# CBB-XBEE-r02.net
KiCad netlist of a schematic drawn in EAGLE
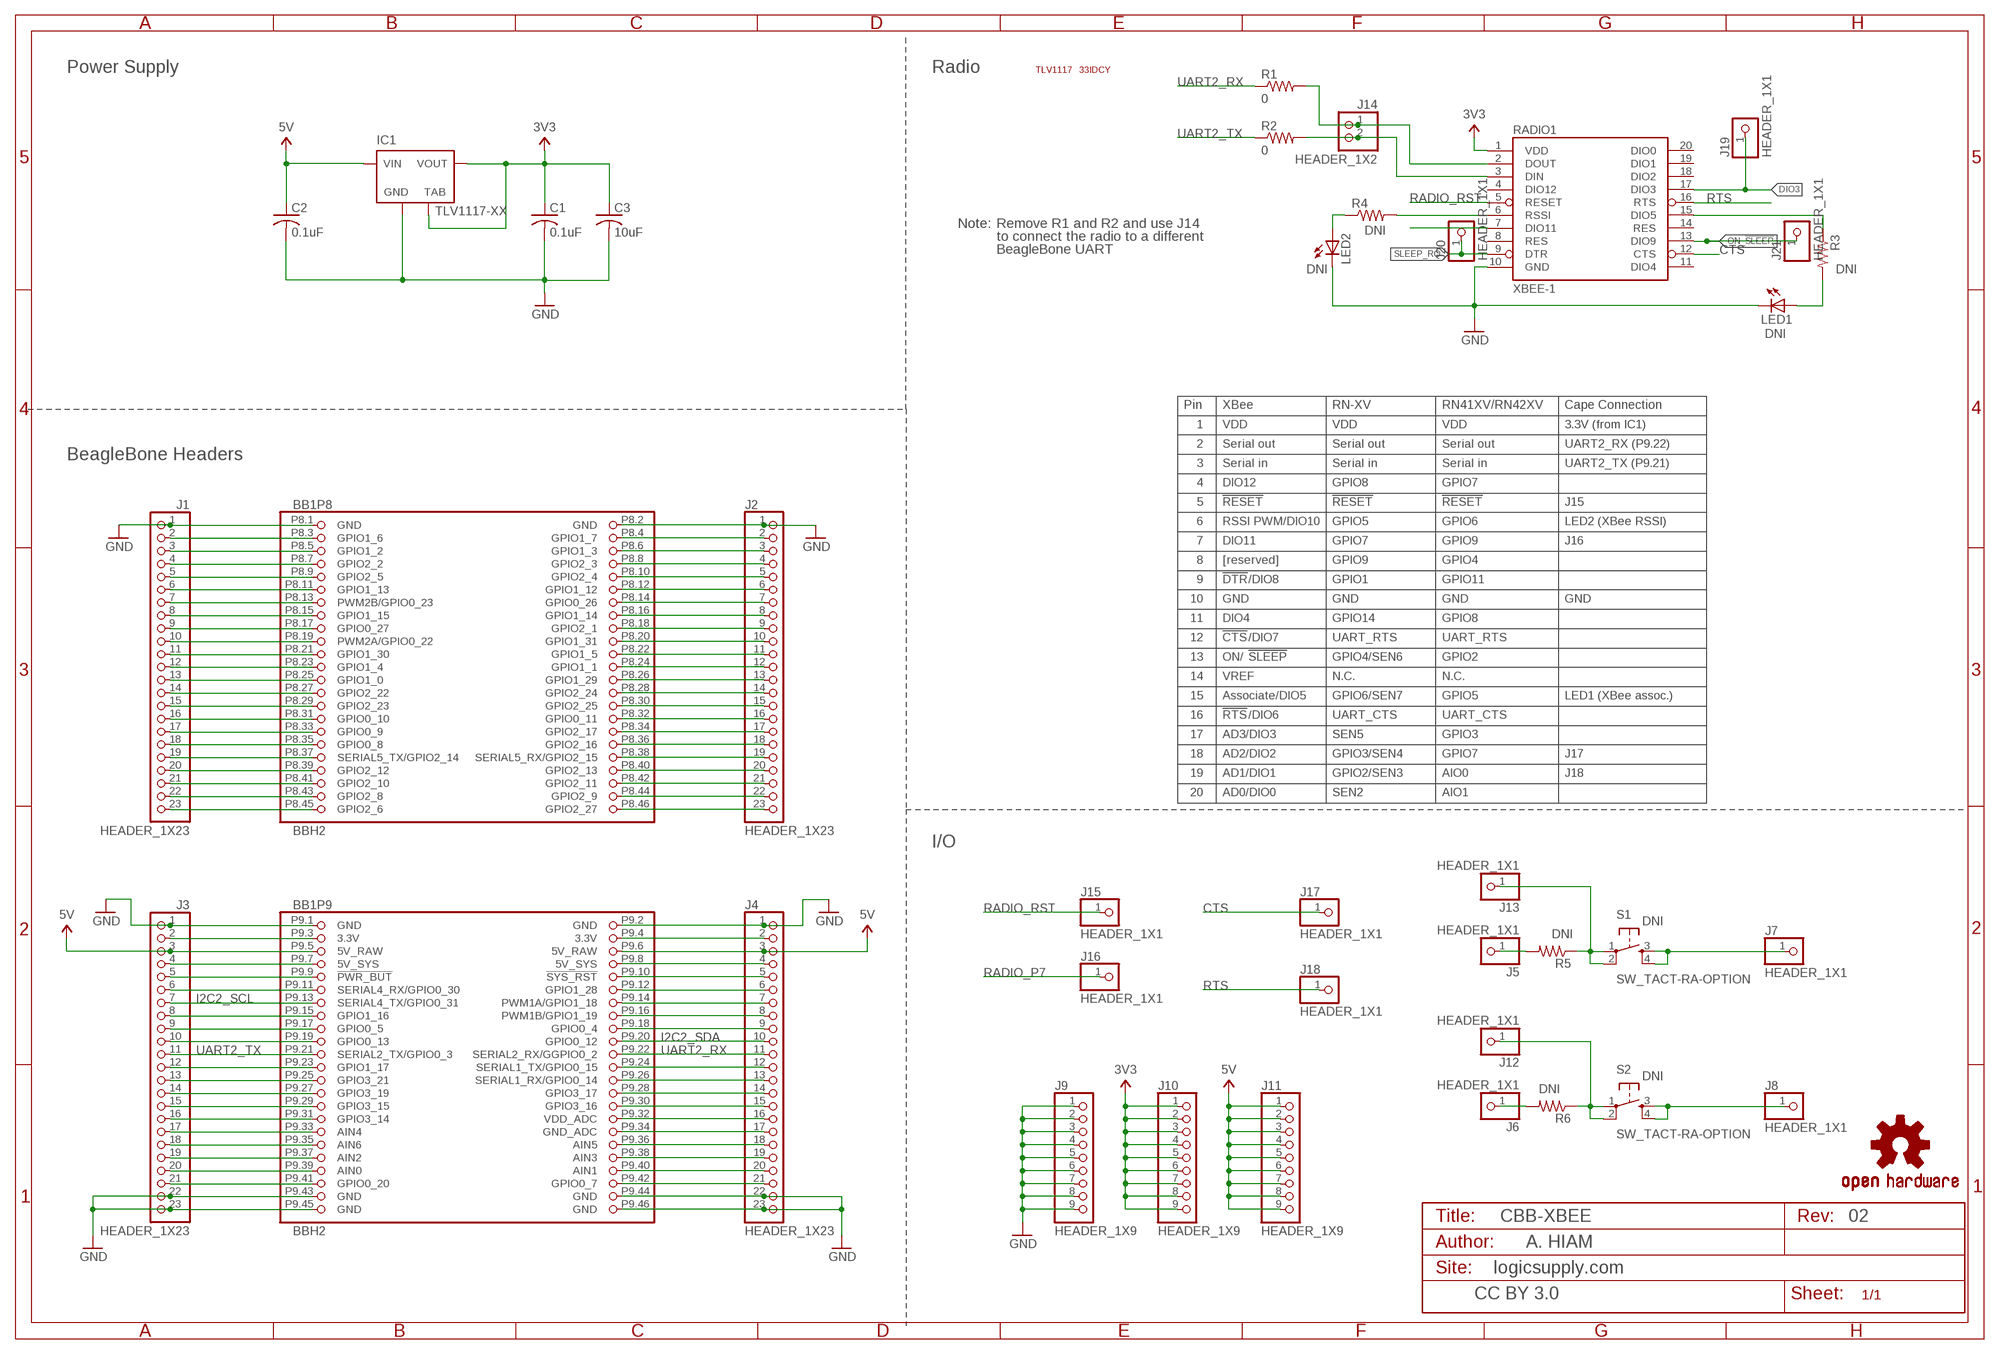
[diagram p0: schematic, sheet 1]

(export (version "E")
  (design (tool "Eeschema 10.0.6"))
  (components
    (comp (ref "BB1")
      (value "BBH2")
      (footprint "eagle-import:BB_CAPE_TOP")
      (libsource (lib "eagle-import") (part "BBH2"))
    )
    (comp (ref "C1")
      (value "0.1uF")
      (footprint "eagle-import:C0805")
      (libsource (lib "eagle-import") (part "C0805"))
    )
    (comp (ref "C2")
      (value "0.1uF")
      (footprint "eagle-import:C0805")
      (libsource (lib "eagle-import") (part "C0805"))
    )
    (comp (ref "C3")
      (value "10uF")
      (footprint "eagle-import:C0805")
      (libsource (lib "eagle-import") (part "C0805"))
    )
    (comp (ref "IC1")
      (value "TLV1117-XX")
      (footprint "eagle-import:SOT223")
      (libsource (lib "eagle-import") (part "TLV1117-XX"))
    )
    (comp (ref "J1")
      (value "HEADER_1X23")
      (footprint "eagle-import:HEADER_1X23")
      (libsource (lib "eagle-import") (part "HEADER_1X23"))
    )
    (comp (ref "J2")
      (value "HEADER_1X23")
      (footprint "eagle-import:HEADER_1X23")
      (libsource (lib "eagle-import") (part "HEADER_1X23"))
    )
    (comp (ref "J3")
      (value "HEADER_1X23")
      (footprint "eagle-import:HEADER_1X23")
      (libsource (lib "eagle-import") (part "HEADER_1X23"))
    )
    (comp (ref "J4")
      (value "HEADER_1X23")
      (footprint "eagle-import:HEADER_1X23")
      (libsource (lib "eagle-import") (part "HEADER_1X23"))
    )
    (comp (ref "J5")
      (value "HEADER_1X1")
      (footprint "eagle-import:HEADER_1X1")
      (libsource (lib "eagle-import") (part "HEADER_1X1"))
    )
    (comp (ref "J6")
      (value "HEADER_1X1")
      (footprint "eagle-import:HEADER_1X1")
      (libsource (lib "eagle-import") (part "HEADER_1X1"))
    )
    (comp (ref "J7")
      (value "HEADER_1X1")
      (footprint "eagle-import:HEADER_1X1")
      (libsource (lib "eagle-import") (part "HEADER_1X1"))
    )
    (comp (ref "J8")
      (value "HEADER_1X1")
      (footprint "eagle-import:HEADER_1X1")
      (libsource (lib "eagle-import") (part "HEADER_1X1"))
    )
    (comp (ref "J9")
      (value "HEADER_1X9")
      (footprint "eagle-import:HEADER_1X9")
      (libsource (lib "eagle-import") (part "HEADER_1X9"))
    )
    (comp (ref "J10")
      (value "HEADER_1X9")
      (footprint "eagle-import:HEADER_1X9")
      (libsource (lib "eagle-import") (part "HEADER_1X9"))
    )
    (comp (ref "J11")
      (value "HEADER_1X9")
      (footprint "eagle-import:HEADER_1X9")
      (libsource (lib "eagle-import") (part "HEADER_1X9"))
    )
    (comp (ref "J12")
      (value "HEADER_1X1")
      (footprint "eagle-import:HEADER_1X1")
      (libsource (lib "eagle-import") (part "HEADER_1X1"))
    )
    (comp (ref "J13")
      (value "HEADER_1X1")
      (footprint "eagle-import:HEADER_1X1")
      (libsource (lib "eagle-import") (part "HEADER_1X1"))
    )
    (comp (ref "J14")
      (value "HEADER_1X2")
      (footprint "eagle-import:HEADER_1X2")
      (libsource (lib "eagle-import") (part "HEADER_1X2"))
    )
    (comp (ref "J15")
      (value "HEADER_1X1")
      (footprint "eagle-import:HEADER_1X1")
      (libsource (lib "eagle-import") (part "HEADER_1X1"))
    )
    (comp (ref "J16")
      (value "HEADER_1X1")
      (footprint "eagle-import:HEADER_1X1")
      (libsource (lib "eagle-import") (part "HEADER_1X1"))
    )
    (comp (ref "J17")
      (value "HEADER_1X1")
      (footprint "eagle-import:HEADER_1X1")
      (libsource (lib "eagle-import") (part "HEADER_1X1"))
    )
    (comp (ref "J18")
      (value "HEADER_1X1")
      (footprint "eagle-import:HEADER_1X1")
      (libsource (lib "eagle-import") (part "HEADER_1X1"))
    )
    (comp (ref "J19")
      (value "HEADER_1X1")
      (footprint "eagle-import:HEADER_1X1")
      (libsource (lib "eagle-import") (part "HEADER_1X1"))
    )
    (comp (ref "J20")
      (value "HEADER_1X1")
      (footprint "eagle-import:HEADER_1X1")
      (libsource (lib "eagle-import") (part "HEADER_1X1"))
    )
    (comp (ref "J21")
      (value "HEADER_1X1")
      (footprint "eagle-import:HEADER_1X1")
      (libsource (lib "eagle-import") (part "HEADER_1X1"))
    )
    (comp (ref "LED1")
      (value "LEDCHIPLED_0805")
      (footprint "eagle-import:CHIPLED_0805")
      (libsource (lib "eagle-import") (part "LEDCHIPLED_0805"))
    )
    (comp (ref "LED2")
      (value "LEDCHIPLED_0805")
      (footprint "eagle-import:CHIPLED_0805")
      (libsource (lib "eagle-import") (part "LEDCHIPLED_0805"))
    )
    (comp (ref "R1")
      (value "0")
      (footprint "eagle-import:R0805")
      (libsource (lib "eagle-import") (part "R0805"))
    )
    (comp (ref "R2")
      (value "0")
      (footprint "eagle-import:R0805")
      (libsource (lib "eagle-import") (part "R0805"))
    )
    (comp (ref "R3")
      (value "R0805")
      (footprint "eagle-import:R0805")
      (libsource (lib "eagle-import") (part "R0805"))
    )
    (comp (ref "R4")
      (value "R0805")
      (footprint "eagle-import:R0805")
      (libsource (lib "eagle-import") (part "R0805"))
    )
    (comp (ref "R5")
      (value "R0207/10")
      (footprint "eagle-import:0207_10")
      (libsource (lib "eagle-import") (part "R0207/10"))
    )
    (comp (ref "R6")
      (value "R0207/10")
      (footprint "eagle-import:0207_10")
      (libsource (lib "eagle-import") (part "R0207/10"))
    )
    (comp (ref "RADIO1")
      (value "XBEE-1")
      (footprint "eagle-import:XBEE")
      (libsource (lib "eagle-import") (part "XBEE-1"))
    )
    (comp (ref "S1")
      (value "SW_TACT-RA-OPTION")
      (footprint "eagle-import:TACT-PTH-RA-OPTION")
      (libsource (lib "eagle-import") (part "SW_TACT-RA-OPTION"))
    )
    (comp (ref "S2")
      (value "SW_TACT-RA-OPTION")
      (footprint "eagle-import:TACT-PTH-RA-OPTION")
      (libsource (lib "eagle-import") (part "SW_TACT-RA-OPTION"))
    )
    (comp (ref "U$7")
      (value "OSHW-LOGOM")
      (footprint "eagle-import:OSHW-LOGO-M")
      (libsource (lib "eagle-import") (part "OSHW-LOGOM"))
    )
  )
  (nets
    (net (code "1") (name "/CTS") (class "Default")
      (node (ref "J17") (pin "1") (pinfunction "1_1") (pintype "passive"))
      (node (ref "RADIO1") (pin "12") (pinfunction "CTS_12") (pintype "output"))
    )
    (net (code "2") (name "/I2C2_SCL") (class "Default")
      (node (ref "BB1") (pin "P9.19") (pinfunction "GPIO0_13_P9.19") (pintype "bidirectional"))
      (node (ref "J3") (pin "10") (pinfunction "10_10") (pintype "passive"))
    )
    (net (code "3") (name "/I2C2_SDA") (class "Default")
      (node (ref "BB1") (pin "P9.20") (pinfunction "GPIO0_12_P9.20") (pintype "bidirectional"))
      (node (ref "J4") (pin "10") (pinfunction "10_10") (pintype "passive"))
    )
    (net (code "4") (name "/ON_~{SLEEP}") (class "Default")
      (node (ref "J21") (pin "1") (pinfunction "1_1") (pintype "passive"))
      (node (ref "RADIO1") (pin "13") (pinfunction "DIO9_13") (pintype "bidirectional"))
    )
    (net (code "5") (name "/RADIO_P7") (class "Default")
      (node (ref "J16") (pin "1") (pinfunction "1_1") (pintype "passive"))
      (node (ref "RADIO1") (pin "7") (pinfunction "DIO11_7") (pintype "bidirectional"))
    )
    (net (code "6") (name "/RADIO_RST") (class "Default")
      (node (ref "J15") (pin "1") (pinfunction "1_1") (pintype "passive"))
      (node (ref "RADIO1") (pin "5") (pinfunction "RESET_5") (pintype "input"))
    )
    (net (code "7") (name "/RTS") (class "Default")
      (node (ref "J18") (pin "1") (pinfunction "1_1") (pintype "passive"))
      (node (ref "RADIO1") (pin "16") (pinfunction "RTS_16") (pintype "input"))
    )
    (net (code "8") (name "/UART2_RX") (class "Default")
      (node (ref "BB1") (pin "P9.22") (pinfunction "SERIAL2_RX/GGPIO0_2_P9.22") (pintype "bidirectional"))
      (node (ref "J4") (pin "11") (pinfunction "11_11") (pintype "passive"))
      (node (ref "R1") (pin "1") (pinfunction "1_1") (pintype "passive"))
    )
    (net (code "9") (name "/UART2_TX") (class "Default")
      (node (ref "BB1") (pin "P9.21") (pinfunction "SERIAL2_TX/GPIO0_3_P9.21") (pintype "bidirectional"))
      (node (ref "J3") (pin "11") (pinfunction "11_11") (pintype "passive"))
      (node (ref "R2") (pin "1") (pinfunction "1_1") (pintype "passive"))
    )
    (net (code "10") (name "3V3") (class "Default")
      (node (ref "C1") (pin "1") (pinfunction "1_1") (pintype "passive"))
      (node (ref "C3") (pin "1") (pinfunction "1_1") (pintype "passive"))
      (node (ref "IC1") (pin "2") (pinfunction "VOUT_2") (pintype "bidirectional"))
      (node (ref "IC1") (pin "4") (pinfunction "TAB_4") (pintype "bidirectional"))
      (node (ref "J10") (pin "1") (pinfunction "1_1") (pintype "passive"))
      (node (ref "J10") (pin "2") (pinfunction "2_2") (pintype "passive"))
      (node (ref "J10") (pin "3") (pinfunction "3_3") (pintype "passive"))
      (node (ref "J10") (pin "4") (pinfunction "4_4") (pintype "passive"))
      (node (ref "J10") (pin "5") (pinfunction "5_5") (pintype "passive"))
      (node (ref "J10") (pin "6") (pinfunction "6_6") (pintype "passive"))
      (node (ref "J10") (pin "7") (pinfunction "7_7") (pintype "passive"))
      (node (ref "J10") (pin "8") (pinfunction "8_8") (pintype "passive"))
      (node (ref "J10") (pin "9") (pinfunction "9_9") (pintype "passive"))
      (node (ref "RADIO1") (pin "1") (pinfunction "VDD_1") (pintype "power_in"))
    )
    (net (code "11") (name "5V") (class "Default")
      (node (ref "BB1") (pin "P9.5") (pinfunction "5V_RAW_P9.5") (pintype "power_in"))
      (node (ref "BB1") (pin "P9.6") (pinfunction "5V_RAW_P9.6") (pintype "power_in"))
      (node (ref "C2") (pin "1") (pinfunction "1_1") (pintype "passive"))
      (node (ref "IC1") (pin "3") (pinfunction "VIN_3") (pintype "bidirectional"))
      (node (ref "J11") (pin "1") (pinfunction "1_1") (pintype "passive"))
      (node (ref "J11") (pin "2") (pinfunction "2_2") (pintype "passive"))
      (node (ref "J11") (pin "3") (pinfunction "3_3") (pintype "passive"))
      (node (ref "J11") (pin "4") (pinfunction "4_4") (pintype "passive"))
      (node (ref "J11") (pin "5") (pinfunction "5_5") (pintype "passive"))
      (node (ref "J11") (pin "6") (pinfunction "6_6") (pintype "passive"))
      (node (ref "J11") (pin "7") (pinfunction "7_7") (pintype "passive"))
      (node (ref "J11") (pin "8") (pinfunction "8_8") (pintype "passive"))
      (node (ref "J11") (pin "9") (pinfunction "9_9") (pintype "passive"))
      (node (ref "J3") (pin "3") (pinfunction "3_3") (pintype "passive"))
      (node (ref "J4") (pin "3") (pinfunction "3_3") (pintype "passive"))
    )
    (net (code "12") (name "DIO3") (class "Default")
      (node (ref "J19") (pin "1") (pinfunction "1_1") (pintype "passive"))
      (node (ref "RADIO1") (pin "17") (pinfunction "DIO3_17") (pintype "bidirectional"))
    )
    (net (code "13") (name "GND") (class "Default")
      (node (ref "BB1") (pin "P8.1") (pinfunction "GND_P8.1") (pintype "power_in"))
      (node (ref "BB1") (pin "P8.2") (pinfunction "GND_P8.2") (pintype "power_in"))
      (node (ref "BB1") (pin "P9.1") (pinfunction "GND_P9.1") (pintype "power_in"))
      (node (ref "BB1") (pin "P9.2") (pinfunction "GND_P9.2") (pintype "power_in"))
      (node (ref "BB1") (pin "P9.43") (pinfunction "GND_P9.43") (pintype "bidirectional"))
      (node (ref "BB1") (pin "P9.44") (pinfunction "GND_P9.44") (pintype "bidirectional"))
      (node (ref "BB1") (pin "P9.45") (pinfunction "GND_P9.45") (pintype "bidirectional"))
      (node (ref "BB1") (pin "P9.46") (pinfunction "GND_P9.46") (pintype "bidirectional"))
      (node (ref "C1") (pin "2") (pinfunction "2_2") (pintype "passive"))
      (node (ref "C2") (pin "2") (pinfunction "2_2") (pintype "passive"))
      (node (ref "C3") (pin "2") (pinfunction "2_2") (pintype "passive"))
      (node (ref "IC1") (pin "1") (pinfunction "GND_1") (pintype "bidirectional"))
      (node (ref "J1") (pin "1") (pinfunction "1_1") (pintype "passive"))
      (node (ref "J2") (pin "1") (pinfunction "1_1") (pintype "passive"))
      (node (ref "J3") (pin "1") (pinfunction "1_1") (pintype "passive"))
      (node (ref "J3") (pin "22") (pinfunction "22_22") (pintype "passive"))
      (node (ref "J3") (pin "23") (pinfunction "23_23") (pintype "passive"))
      (node (ref "J4") (pin "1") (pinfunction "1_1") (pintype "passive"))
      (node (ref "J4") (pin "22") (pinfunction "22_22") (pintype "passive"))
      (node (ref "J4") (pin "23") (pinfunction "23_23") (pintype "passive"))
      (node (ref "J9") (pin "1") (pinfunction "1_1") (pintype "passive"))
      (node (ref "J9") (pin "2") (pinfunction "2_2") (pintype "passive"))
      (node (ref "J9") (pin "3") (pinfunction "3_3") (pintype "passive"))
      (node (ref "J9") (pin "4") (pinfunction "4_4") (pintype "passive"))
      (node (ref "J9") (pin "5") (pinfunction "5_5") (pintype "passive"))
      (node (ref "J9") (pin "6") (pinfunction "6_6") (pintype "passive"))
      (node (ref "J9") (pin "7") (pinfunction "7_7") (pintype "passive"))
      (node (ref "J9") (pin "8") (pinfunction "8_8") (pintype "passive"))
      (node (ref "J9") (pin "9") (pinfunction "9_9") (pintype "passive"))
      (node (ref "LED1") (pin "C") (pinfunction "C_C") (pintype "passive"))
      (node (ref "LED2") (pin "C") (pinfunction "C_C") (pintype "passive"))
      (node (ref "RADIO1") (pin "10") (pinfunction "GND_10") (pintype "power_in"))
    )
    (net (code "14") (name "Net-(BB1A-GPIO0_8)") (class "Default")
      (node (ref "BB1") (pin "P8.35") (pinfunction "GPIO0_8_P8.35") (pintype "bidirectional"))
      (node (ref "J1") (pin "18") (pinfunction "18_18") (pintype "passive"))
    )
    (net (code "15") (name "Net-(BB1A-GPIO0_9)") (class "Default")
      (node (ref "BB1") (pin "P8.33") (pinfunction "GPIO0_9_P8.33") (pintype "bidirectional"))
      (node (ref "J1") (pin "17") (pinfunction "17_17") (pintype "passive"))
    )
    (net (code "16") (name "Net-(BB1A-GPIO0_10)") (class "Default")
      (node (ref "BB1") (pin "P8.31") (pinfunction "GPIO0_10_P8.31") (pintype "bidirectional"))
      (node (ref "J1") (pin "16") (pinfunction "16_16") (pintype "passive"))
    )
    (net (code "17") (name "Net-(BB1A-GPIO0_11)") (class "Default")
      (node (ref "BB1") (pin "P8.32") (pinfunction "GPIO0_11_P8.32") (pintype "bidirectional"))
      (node (ref "J2") (pin "16") (pinfunction "16_16") (pintype "passive"))
    )
    (net (code "18") (name "Net-(BB1A-GPIO0_26)") (class "Default")
      (node (ref "BB1") (pin "P8.14") (pinfunction "GPIO0_26_P8.14") (pintype "bidirectional"))
      (node (ref "J2") (pin "7") (pinfunction "7_7") (pintype "passive"))
    )
    (net (code "19") (name "Net-(BB1A-GPIO0_27)") (class "Default")
      (node (ref "BB1") (pin "P8.17") (pinfunction "GPIO0_27_P8.17") (pintype "bidirectional"))
      (node (ref "J1") (pin "9") (pinfunction "9_9") (pintype "passive"))
    )
    (net (code "20") (name "Net-(BB1A-GPIO1_0)") (class "Default")
      (node (ref "BB1") (pin "P8.25") (pinfunction "GPIO1_0_P8.25") (pintype "bidirectional"))
      (node (ref "J1") (pin "13") (pinfunction "13_13") (pintype "passive"))
    )
    (net (code "21") (name "Net-(BB1A-GPIO1_1)") (class "Default")
      (node (ref "BB1") (pin "P8.24") (pinfunction "GPIO1_1_P8.24") (pintype "bidirectional"))
      (node (ref "J2") (pin "12") (pinfunction "12_12") (pintype "passive"))
    )
    (net (code "22") (name "Net-(BB1A-GPIO1_2)") (class "Default")
      (node (ref "BB1") (pin "P8.5") (pinfunction "GPIO1_2_P8.5") (pintype "bidirectional"))
      (node (ref "J1") (pin "3") (pinfunction "3_3") (pintype "passive"))
    )
    (net (code "23") (name "Net-(BB1A-GPIO1_3)") (class "Default")
      (node (ref "BB1") (pin "P8.6") (pinfunction "GPIO1_3_P8.6") (pintype "bidirectional"))
      (node (ref "J2") (pin "3") (pinfunction "3_3") (pintype "passive"))
    )
    (net (code "24") (name "Net-(BB1A-GPIO1_4)") (class "Default")
      (node (ref "BB1") (pin "P8.23") (pinfunction "GPIO1_4_P8.23") (pintype "bidirectional"))
      (node (ref "J1") (pin "12") (pinfunction "12_12") (pintype "passive"))
    )
    (net (code "25") (name "Net-(BB1A-GPIO1_5)") (class "Default")
      (node (ref "BB1") (pin "P8.22") (pinfunction "GPIO1_5_P8.22") (pintype "bidirectional"))
      (node (ref "J2") (pin "11") (pinfunction "11_11") (pintype "passive"))
    )
    (net (code "26") (name "Net-(BB1A-GPIO1_6)") (class "Default")
      (node (ref "BB1") (pin "P8.3") (pinfunction "GPIO1_6_P8.3") (pintype "bidirectional"))
      (node (ref "J1") (pin "2") (pinfunction "2_2") (pintype "passive"))
    )
    (net (code "27") (name "Net-(BB1A-GPIO1_7)") (class "Default")
      (node (ref "BB1") (pin "P8.4") (pinfunction "GPIO1_7_P8.4") (pintype "bidirectional"))
      (node (ref "J2") (pin "2") (pinfunction "2_2") (pintype "passive"))
    )
    (net (code "28") (name "Net-(BB1A-GPIO1_12)") (class "Default")
      (node (ref "BB1") (pin "P8.12") (pinfunction "GPIO1_12_P8.12") (pintype "bidirectional"))
      (node (ref "J2") (pin "6") (pinfunction "6_6") (pintype "passive"))
    )
    (net (code "29") (name "Net-(BB1A-GPIO1_13)") (class "Default")
      (node (ref "BB1") (pin "P8.11") (pinfunction "GPIO1_13_P8.11") (pintype "bidirectional"))
      (node (ref "J1") (pin "6") (pinfunction "6_6") (pintype "passive"))
    )
    (net (code "30") (name "Net-(BB1A-GPIO1_14)") (class "Default")
      (node (ref "BB1") (pin "P8.16") (pinfunction "GPIO1_14_P8.16") (pintype "bidirectional"))
      (node (ref "J2") (pin "8") (pinfunction "8_8") (pintype "passive"))
    )
    (net (code "31") (name "Net-(BB1A-GPIO1_15)") (class "Default")
      (node (ref "BB1") (pin "P8.15") (pinfunction "GPIO1_15_P8.15") (pintype "bidirectional"))
      (node (ref "J1") (pin "8") (pinfunction "8_8") (pintype "passive"))
    )
    (net (code "32") (name "Net-(BB1A-GPIO1_29)") (class "Default")
      (node (ref "BB1") (pin "P8.26") (pinfunction "GPIO1_29_P8.26") (pintype "bidirectional"))
      (node (ref "J2") (pin "13") (pinfunction "13_13") (pintype "passive"))
    )
    (net (code "33") (name "Net-(BB1A-GPIO1_30)") (class "Default")
      (node (ref "BB1") (pin "P8.21") (pinfunction "GPIO1_30_P8.21") (pintype "bidirectional"))
      (node (ref "J1") (pin "11") (pinfunction "11_11") (pintype "passive"))
    )
    (net (code "34") (name "Net-(BB1A-GPIO1_31)") (class "Default")
      (node (ref "BB1") (pin "P8.20") (pinfunction "GPIO1_31_P8.20") (pintype "bidirectional"))
      (node (ref "J2") (pin "10") (pinfunction "10_10") (pintype "passive"))
    )
    (net (code "35") (name "Net-(BB1A-GPIO2_1)") (class "Default")
      (node (ref "BB1") (pin "P8.18") (pinfunction "GPIO2_1_P8.18") (pintype "bidirectional"))
      (node (ref "J2") (pin "9") (pinfunction "9_9") (pintype "passive"))
    )
    (net (code "36") (name "Net-(BB1A-GPIO2_2)") (class "Default")
      (node (ref "BB1") (pin "P8.7") (pinfunction "GPIO2_2_P8.7") (pintype "bidirectional"))
      (node (ref "J1") (pin "4") (pinfunction "4_4") (pintype "passive"))
    )
    (net (code "37") (name "Net-(BB1A-GPIO2_3)") (class "Default")
      (node (ref "BB1") (pin "P8.8") (pinfunction "GPIO2_3_P8.8") (pintype "bidirectional"))
      (node (ref "J2") (pin "4") (pinfunction "4_4") (pintype "passive"))
    )
    (net (code "38") (name "Net-(BB1A-GPIO2_4)") (class "Default")
      (node (ref "BB1") (pin "P8.10") (pinfunction "GPIO2_4_P8.10") (pintype "bidirectional"))
      (node (ref "J2") (pin "5") (pinfunction "5_5") (pintype "passive"))
    )
    (net (code "39") (name "Net-(BB1A-GPIO2_5)") (class "Default")
      (node (ref "BB1") (pin "P8.9") (pinfunction "GPIO2_5_P8.9") (pintype "bidirectional"))
      (node (ref "J1") (pin "5") (pinfunction "5_5") (pintype "passive"))
    )
    (net (code "40") (name "Net-(BB1A-GPIO2_6)") (class "Default")
      (node (ref "BB1") (pin "P8.45") (pinfunction "GPIO2_6_P8.45") (pintype "bidirectional"))
      (node (ref "J1") (pin "23") (pinfunction "23_23") (pintype "passive"))
    )
    (net (code "41") (name "Net-(BB1A-GPIO2_8)") (class "Default")
      (node (ref "BB1") (pin "P8.43") (pinfunction "GPIO2_8_P8.43") (pintype "bidirectional"))
      (node (ref "J1") (pin "22") (pinfunction "22_22") (pintype "passive"))
    )
    (net (code "42") (name "Net-(BB1A-GPIO2_9)") (class "Default")
      (node (ref "BB1") (pin "P8.44") (pinfunction "GPIO2_9_P8.44") (pintype "bidirectional"))
      (node (ref "J2") (pin "22") (pinfunction "22_22") (pintype "passive"))
    )
    (net (code "43") (name "Net-(BB1A-GPIO2_10)") (class "Default")
      (node (ref "BB1") (pin "P8.41") (pinfunction "GPIO2_10_P8.41") (pintype "bidirectional"))
      (node (ref "J1") (pin "21") (pinfunction "21_21") (pintype "passive"))
    )
    (net (code "44") (name "Net-(BB1A-GPIO2_11)") (class "Default")
      (node (ref "BB1") (pin "P8.42") (pinfunction "GPIO2_11_P8.42") (pintype "bidirectional"))
      (node (ref "J2") (pin "21") (pinfunction "21_21") (pintype "passive"))
    )
    (net (code "45") (name "Net-(BB1A-GPIO2_12)") (class "Default")
      (node (ref "BB1") (pin "P8.39") (pinfunction "GPIO2_12_P8.39") (pintype "bidirectional"))
      (node (ref "J1") (pin "20") (pinfunction "20_20") (pintype "passive"))
    )
    (net (code "46") (name "Net-(BB1A-GPIO2_13)") (class "Default")
      (node (ref "BB1") (pin "P8.40") (pinfunction "GPIO2_13_P8.40") (pintype "bidirectional"))
      (node (ref "J2") (pin "20") (pinfunction "20_20") (pintype "passive"))
    )
    (net (code "47") (name "Net-(BB1A-GPIO2_16)") (class "Default")
      (node (ref "BB1") (pin "P8.36") (pinfunction "GPIO2_16_P8.36") (pintype "bidirectional"))
      (node (ref "J2") (pin "18") (pinfunction "18_18") (pintype "passive"))
    )
    (net (code "48") (name "Net-(BB1A-GPIO2_17)") (class "Default")
      (node (ref "BB1") (pin "P8.34") (pinfunction "GPIO2_17_P8.34") (pintype "bidirectional"))
      (node (ref "J2") (pin "17") (pinfunction "17_17") (pintype "passive"))
    )
    (net (code "49") (name "Net-(BB1A-GPIO2_22)") (class "Default")
      (node (ref "BB1") (pin "P8.27") (pinfunction "GPIO2_22_P8.27") (pintype "bidirectional"))
      (node (ref "J1") (pin "14") (pinfunction "14_14") (pintype "passive"))
    )
    (net (code "50") (name "Net-(BB1A-GPIO2_23)") (class "Default")
      (node (ref "BB1") (pin "P8.29") (pinfunction "GPIO2_23_P8.29") (pintype "bidirectional"))
      (node (ref "J1") (pin "15") (pinfunction "15_15") (pintype "passive"))
    )
    (net (code "51") (name "Net-(BB1A-GPIO2_24)") (class "Default")
      (node (ref "BB1") (pin "P8.28") (pinfunction "GPIO2_24_P8.28") (pintype "bidirectional"))
      (node (ref "J2") (pin "14") (pinfunction "14_14") (pintype "passive"))
    )
    (net (code "52") (name "Net-(BB1A-GPIO2_25)") (class "Default")
      (node (ref "BB1") (pin "P8.30") (pinfunction "GPIO2_25_P8.30") (pintype "bidirectional"))
      (node (ref "J2") (pin "15") (pinfunction "15_15") (pintype "passive"))
    )
    (net (code "53") (name "Net-(BB1A-GPIO2_27)") (class "Default")
      (node (ref "BB1") (pin "P8.46") (pinfunction "GPIO2_27_P8.46") (pintype "bidirectional"))
      (node (ref "J2") (pin "23") (pinfunction "23_23") (pintype "passive"))
    )
    (net (code "54") (name "Net-(BB1A-PWM2A{slash}GPIO0_22)") (class "Default")
      (node (ref "BB1") (pin "P8.19") (pinfunction "PWM2A/GPIO0_22_P8.19") (pintype "bidirectional"))
      (node (ref "J1") (pin "10") (pinfunction "10_10") (pintype "passive"))
    )
    (net (code "55") (name "Net-(BB1A-PWM2B{slash}GPIO0_23)") (class "Default")
      (node (ref "BB1") (pin "P8.13") (pinfunction "PWM2B/GPIO0_23_P8.13") (pintype "bidirectional"))
      (node (ref "J1") (pin "7") (pinfunction "7_7") (pintype "passive"))
    )
    (net (code "56") (name "Net-(BB1A-SERIAL5_RX{slash}GPIO2_15)") (class "Default")
      (node (ref "BB1") (pin "P8.38") (pinfunction "SERIAL5_RX/GPIO2_15_P8.38") (pintype "bidirectional"))
      (node (ref "J2") (pin "19") (pinfunction "19_19") (pintype "passive"))
    )
    (net (code "57") (name "Net-(BB1A-SERIAL5_TX{slash}GPIO2_14)") (class "Default")
      (node (ref "BB1") (pin "P8.37") (pinfunction "SERIAL5_TX/GPIO2_14_P8.37") (pintype "bidirectional"))
      (node (ref "J1") (pin "19") (pinfunction "19_19") (pintype "passive"))
    )
    (net (code "58") (name "Net-(BB1B-3.3V-PadP9.3)") (class "Default")
      (node (ref "BB1") (pin "P9.3") (pinfunction "3.3V_P9.3") (pintype "power_in"))
      (node (ref "J3") (pin "2") (pinfunction "2_2") (pintype "passive"))
    )
    (net (code "59") (name "Net-(BB1B-3.3V-PadP9.4)") (class "Default")
      (node (ref "BB1") (pin "P9.4") (pinfunction "3.3V_P9.4") (pintype "power_in"))
      (node (ref "J4") (pin "2") (pinfunction "2_2") (pintype "passive"))
    )
    (net (code "60") (name "Net-(BB1B-5V_SYS-PadP9.7)") (class "Default")
      (node (ref "BB1") (pin "P9.7") (pinfunction "5V_SYS_P9.7") (pintype "power_in"))
      (node (ref "J3") (pin "4") (pinfunction "4_4") (pintype "passive"))
    )
    (net (code "61") (name "Net-(BB1B-5V_SYS-PadP9.8)") (class "Default")
      (node (ref "BB1") (pin "P9.8") (pinfunction "5V_SYS_P9.8") (pintype "power_in"))
      (node (ref "J4") (pin "4") (pinfunction "4_4") (pintype "passive"))
    )
    (net (code "62") (name "Net-(BB1B-AIN0)") (class "Default")
      (node (ref "BB1") (pin "P9.39") (pinfunction "AIN0_P9.39") (pintype "input"))
      (node (ref "J3") (pin "20") (pinfunction "20_20") (pintype "passive"))
    )
    (net (code "63") (name "Net-(BB1B-AIN1)") (class "Default")
      (node (ref "BB1") (pin "P9.40") (pinfunction "AIN1_P9.40") (pintype "input"))
      (node (ref "J4") (pin "20") (pinfunction "20_20") (pintype "passive"))
    )
    (net (code "64") (name "Net-(BB1B-AIN2)") (class "Default")
      (node (ref "BB1") (pin "P9.37") (pinfunction "AIN2_P9.37") (pintype "input"))
      (node (ref "J3") (pin "19") (pinfunction "19_19") (pintype "passive"))
    )
    (net (code "65") (name "Net-(BB1B-AIN3)") (class "Default")
      (node (ref "BB1") (pin "P9.38") (pinfunction "AIN3_P9.38") (pintype "input"))
      (node (ref "J4") (pin "19") (pinfunction "19_19") (pintype "passive"))
    )
    (net (code "66") (name "Net-(BB1B-AIN4)") (class "Default")
      (node (ref "BB1") (pin "P9.33") (pinfunction "AIN4_P9.33") (pintype "input"))
      (node (ref "J3") (pin "17") (pinfunction "17_17") (pintype "passive"))
    )
    (net (code "67") (name "Net-(BB1B-AIN5)") (class "Default")
      (node (ref "BB1") (pin "P9.36") (pinfunction "AIN5_P9.36") (pintype "input"))
      (node (ref "J4") (pin "18") (pinfunction "18_18") (pintype "passive"))
    )
    (net (code "68") (name "Net-(BB1B-AIN6)") (class "Default")
      (node (ref "BB1") (pin "P9.35") (pinfunction "AIN6_P9.35") (pintype "input"))
      (node (ref "J3") (pin "18") (pinfunction "18_18") (pintype "passive"))
    )
    (net (code "69") (name "Net-(BB1B-GND_ADC)") (class "Default")
      (node (ref "BB1") (pin "P9.34") (pinfunction "GND_ADC_P9.34") (pintype "bidirectional"))
      (node (ref "J4") (pin "17") (pinfunction "17_17") (pintype "passive"))
    )
    (net (code "70") (name "Net-(BB1B-GPIO0_4)") (class "Default")
      (node (ref "BB1") (pin "P9.18") (pinfunction "GPIO0_4_P9.18") (pintype "bidirectional"))
      (node (ref "J4") (pin "9") (pinfunction "9_9") (pintype "passive"))
    )
    (net (code "71") (name "Net-(BB1B-GPIO0_5)") (class "Default")
      (node (ref "BB1") (pin "P9.17") (pinfunction "GPIO0_5_P9.17") (pintype "bidirectional"))
      (node (ref "J3") (pin "9") (pinfunction "9_9") (pintype "passive"))
    )
    (net (code "72") (name "Net-(BB1B-GPIO0_7)") (class "Default")
      (node (ref "BB1") (pin "P9.42") (pinfunction "GPIO0_7_P9.42") (pintype "bidirectional"))
      (node (ref "J4") (pin "21") (pinfunction "21_21") (pintype "passive"))
    )
    (net (code "73") (name "Net-(BB1B-GPIO0_20)") (class "Default")
      (node (ref "BB1") (pin "P9.41") (pinfunction "GPIO0_20_P9.41") (pintype "bidirectional"))
      (node (ref "J3") (pin "21") (pinfunction "21_21") (pintype "passive"))
    )
    (net (code "74") (name "Net-(BB1B-GPIO1_16)") (class "Default")
      (node (ref "BB1") (pin "P9.15") (pinfunction "GPIO1_16_P9.15") (pintype "bidirectional"))
      (node (ref "J3") (pin "8") (pinfunction "8_8") (pintype "passive"))
    )
    (net (code "75") (name "Net-(BB1B-GPIO1_17)") (class "Default")
      (node (ref "BB1") (pin "P9.23") (pinfunction "GPIO1_17_P9.23") (pintype "bidirectional"))
      (node (ref "J3") (pin "12") (pinfunction "12_12") (pintype "passive"))
    )
    (net (code "76") (name "Net-(BB1B-GPIO1_28)") (class "Default")
      (node (ref "BB1") (pin "P9.12") (pinfunction "GPIO1_28_P9.12") (pintype "bidirectional"))
      (node (ref "J4") (pin "6") (pinfunction "6_6") (pintype "passive"))
    )
    (net (code "77") (name "Net-(BB1B-GPIO3_14)") (class "Default")
      (node (ref "BB1") (pin "P9.31") (pinfunction "GPIO3_14_P9.31") (pintype "bidirectional"))
      (node (ref "J3") (pin "16") (pinfunction "16_16") (pintype "passive"))
    )
    (net (code "78") (name "Net-(BB1B-GPIO3_15)") (class "Default")
      (node (ref "BB1") (pin "P9.29") (pinfunction "GPIO3_15_P9.29") (pintype "bidirectional"))
      (node (ref "J3") (pin "15") (pinfunction "15_15") (pintype "passive"))
    )
    (net (code "79") (name "Net-(BB1B-GPIO3_16)") (class "Default")
      (node (ref "BB1") (pin "P9.30") (pinfunction "GPIO3_16_P9.30") (pintype "bidirectional"))
      (node (ref "J4") (pin "15") (pinfunction "15_15") (pintype "passive"))
    )
    (net (code "80") (name "Net-(BB1B-GPIO3_17)") (class "Default")
      (node (ref "BB1") (pin "P9.28") (pinfunction "GPIO3_17_P9.28") (pintype "bidirectional"))
      (node (ref "J4") (pin "14") (pinfunction "14_14") (pintype "passive"))
    )
    (net (code "81") (name "Net-(BB1B-GPIO3_19)") (class "Default")
      (node (ref "BB1") (pin "P9.27") (pinfunction "GPIO3_19_P9.27") (pintype "bidirectional"))
      (node (ref "J3") (pin "14") (pinfunction "14_14") (pintype "passive"))
    )
    (net (code "82") (name "Net-(BB1B-GPIO3_21)") (class "Default")
      (node (ref "BB1") (pin "P9.25") (pinfunction "GPIO3_21_P9.25") (pintype "bidirectional"))
      (node (ref "J3") (pin "13") (pinfunction "13_13") (pintype "passive"))
    )
    (net (code "83") (name "Net-(BB1B-PWM1A{slash}GPIO1_18)") (class "Default")
      (node (ref "BB1") (pin "P9.14") (pinfunction "PWM1A/GPIO1_18_P9.14") (pintype "bidirectional"))
      (node (ref "J4") (pin "7") (pinfunction "7_7") (pintype "passive"))
    )
    (net (code "84") (name "Net-(BB1B-PWM1B{slash}GPIO1_19)") (class "Default")
      (node (ref "BB1") (pin "P9.16") (pinfunction "PWM1B/GPIO1_19_P9.16") (pintype "bidirectional"))
      (node (ref "J4") (pin "8") (pinfunction "8_8") (pintype "passive"))
    )
    (net (code "85") (name "Net-(BB1B-SERIAL1_RX{slash}GPIO0_14)") (class "Default")
      (node (ref "BB1") (pin "P9.26") (pinfunction "SERIAL1_RX/GPIO0_14_P9.26") (pintype "bidirectional"))
      (node (ref "J4") (pin "13") (pinfunction "13_13") (pintype "passive"))
    )
    (net (code "86") (name "Net-(BB1B-SERIAL1_TX{slash}GPIO0_15)") (class "Default")
      (node (ref "BB1") (pin "P9.24") (pinfunction "SERIAL1_TX/GPIO0_15_P9.24") (pintype "bidirectional"))
      (node (ref "J4") (pin "12") (pinfunction "12_12") (pintype "passive"))
    )
    (net (code "87") (name "Net-(BB1B-SERIAL4_RX{slash}GPIO0_30)") (class "Default")
      (node (ref "BB1") (pin "P9.11") (pinfunction "SERIAL4_RX/GPIO0_30_P9.11") (pintype "bidirectional"))
      (node (ref "J3") (pin "6") (pinfunction "6_6") (pintype "passive"))
    )
    (net (code "88") (name "Net-(BB1B-SERIAL4_TX{slash}GPIO0_31)") (class "Default")
      (node (ref "BB1") (pin "P9.13") (pinfunction "SERIAL4_TX/GPIO0_31_P9.13") (pintype "bidirectional"))
      (node (ref "J3") (pin "7") (pinfunction "7_7") (pintype "passive"))
    )
    (net (code "89") (name "Net-(BB1B-VDD_ADC)") (class "Default")
      (node (ref "BB1") (pin "P9.32") (pinfunction "VDD_ADC_P9.32") (pintype "bidirectional"))
      (node (ref "J4") (pin "16") (pinfunction "16_16") (pintype "passive"))
    )
    (net (code "90") (name "Net-(BB1B-~{PWR_BUT})") (class "Default")
      (node (ref "BB1") (pin "P9.9") (pinfunction "~{PWR_BUT}_P9.9") (pintype "input"))
      (node (ref "J3") (pin "5") (pinfunction "5_5") (pintype "passive"))
    )
    (net (code "91") (name "Net-(BB1B-~{SYS_RST})") (class "Default")
      (node (ref "BB1") (pin "P9.10") (pinfunction "~{SYS_RST}_P9.10") (pintype "input"))
      (node (ref "J4") (pin "5") (pinfunction "5_5") (pintype "passive"))
    )
    (net (code "92") (name "Net-(J5-Pad1)") (class "Default")
      (node (ref "J5") (pin "1") (pinfunction "1_1") (pintype "passive"))
      (node (ref "R5") (pin "2") (pinfunction "2_2") (pintype "passive"))
    )
    (net (code "93") (name "Net-(J6-Pad1)") (class "Default")
      (node (ref "J6") (pin "1") (pinfunction "1_1") (pintype "passive"))
      (node (ref "R6") (pin "2") (pinfunction "2_2") (pintype "passive"))
    )
    (net (code "94") (name "Net-(J7-Pad1)") (class "Default")
      (node (ref "J7") (pin "1") (pinfunction "1_1") (pintype "passive"))
      (node (ref "S1") (pin "3") (pinfunction "3_3") (pintype "passive"))
      (node (ref "S1") (pin "4") (pinfunction "4_4") (pintype "passive"))
    )
    (net (code "95") (name "Net-(J8-Pad1)") (class "Default")
      (node (ref "J8") (pin "1") (pinfunction "1_1") (pintype "passive"))
      (node (ref "S2") (pin "3") (pinfunction "3_3") (pintype "passive"))
      (node (ref "S2") (pin "4") (pinfunction "4_4") (pintype "passive"))
    )
    (net (code "96") (name "Net-(J12-Pad1)") (class "Default")
      (node (ref "J12") (pin "1") (pinfunction "1_1") (pintype "passive"))
      (node (ref "R6") (pin "1") (pinfunction "1_1") (pintype "passive"))
      (node (ref "S2") (pin "1") (pinfunction "1_1") (pintype "passive"))
      (node (ref "S2") (pin "2") (pinfunction "2_2") (pintype "passive"))
    )
    (net (code "97") (name "Net-(J13-Pad1)") (class "Default")
      (node (ref "J13") (pin "1") (pinfunction "1_1") (pintype "passive"))
      (node (ref "R5") (pin "1") (pinfunction "1_1") (pintype "passive"))
      (node (ref "S1") (pin "1") (pinfunction "1_1") (pintype "passive"))
      (node (ref "S1") (pin "2") (pinfunction "2_2") (pintype "passive"))
    )
    (net (code "98") (name "Net-(LED1-PadA)") (class "Default")
      (node (ref "LED1") (pin "A") (pinfunction "A_A") (pintype "passive"))
      (node (ref "R3") (pin "2") (pinfunction "2_2") (pintype "passive"))
    )
    (net (code "99") (name "Net-(LED2-PadA)") (class "Default")
      (node (ref "LED2") (pin "A") (pinfunction "A_A") (pintype "passive"))
      (node (ref "R4") (pin "1") (pinfunction "1_1") (pintype "passive"))
    )
    (net (code "100") (name "Net-(RADIO1-DIN)") (class "Default")
      (node (ref "J14") (pin "2") (pinfunction "2_2") (pintype "passive"))
      (node (ref "R2") (pin "2") (pinfunction "2_2") (pintype "passive"))
      (node (ref "RADIO1") (pin "3") (pinfunction "DIN_3") (pintype "input"))
    )
    (net (code "101") (name "Net-(RADIO1-DIO5)") (class "Default")
      (node (ref "R3") (pin "1") (pinfunction "1_1") (pintype "passive"))
      (node (ref "RADIO1") (pin "15") (pinfunction "DIO5_15") (pintype "bidirectional"))
    )
    (net (code "102") (name "Net-(RADIO1-DOUT)") (class "Default")
      (node (ref "J14") (pin "1") (pinfunction "1_1") (pintype "passive"))
      (node (ref "R1") (pin "2") (pinfunction "2_2") (pintype "passive"))
      (node (ref "RADIO1") (pin "2") (pinfunction "DOUT_2") (pintype "output"))
    )
    (net (code "103") (name "Net-(RADIO1-RSSI)") (class "Default")
      (node (ref "R4") (pin "2") (pinfunction "2_2") (pintype "passive"))
      (node (ref "RADIO1") (pin "6") (pinfunction "RSSI_6") (pintype "bidirectional"))
    )
    (net (code "104") (name "SLEEP_RQ") (class "Default")
      (node (ref "J20") (pin "1") (pinfunction "1_1") (pintype "passive"))
      (node (ref "RADIO1") (pin "9") (pinfunction "DTR_9") (pintype "bidirectional"))
    )
    (net (code "105") (name "unconnected-(RADIO1-DIO0-Pad20)") (class "Default")
      (node (ref "RADIO1") (pin "20") (pinfunction "DIO0_20") (pintype "bidirectional"))
    )
    (net (code "106") (name "unconnected-(RADIO1-DIO1-Pad19)") (class "Default")
      (node (ref "RADIO1") (pin "19") (pinfunction "DIO1_19") (pintype "bidirectional"))
    )
    (net (code "107") (name "unconnected-(RADIO1-DIO2-Pad18)") (class "Default")
      (node (ref "RADIO1") (pin "18") (pinfunction "DIO2_18") (pintype "bidirectional"))
    )
    (net (code "108") (name "unconnected-(RADIO1-DIO4-Pad11)") (class "Default")
      (node (ref "RADIO1") (pin "11") (pinfunction "DIO4_11") (pintype "bidirectional"))
    )
    (net (code "109") (name "unconnected-(RADIO1-DIO12-Pad4)") (class "Default")
      (node (ref "RADIO1") (pin "4") (pinfunction "DIO12_4") (pintype "bidirectional"))
    )
    (net (code "110") (name "unconnected-(RADIO1-RES-Pad8)") (class "Default")
      (node (ref "RADIO1") (pin "8") (pinfunction "RES_8") (pintype "bidirectional"))
    )
    (net (code "111") (name "unconnected-(RADIO1-RES-Pad14)") (class "Default")
      (node (ref "RADIO1") (pin "14") (pinfunction "RES_14") (pintype "bidirectional"))
    )
  )
)
